# LPS33HW_breakout.net
KiCad netlist of a schematic drawn in EAGLE
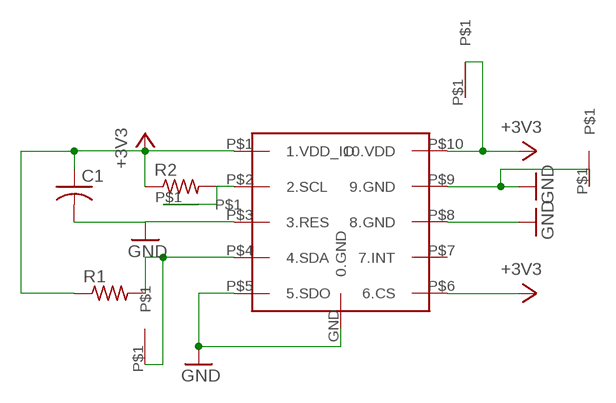
[diagram p0: schematic, sheet 1]

(export (version "E")
  (design (tool "Eeschema 10.0.6"))
  (components
    (comp (ref "C1")
      (value "C-USC0402")
      (footprint "eagle-import:C0402")
      (libsource (lib "eagle-import") (part "C-USC0402"))
    )
    (comp (ref "R1")
      (value "R-US_R0402")
      (footprint "eagle-import:R0402")
      (libsource (lib "eagle-import") (part "R-US_R0402"))
    )
    (comp (ref "R2")
      (value "R-US_R0402")
      (footprint "eagle-import:R0402")
      (libsource (lib "eagle-import") (part "R-US_R0402"))
    )
    (comp (ref "U$1")
      (value "LPS33HW")
      (footprint "eagle-import:LPS33HW")
      (libsource (lib "eagle-import") (part "LPS33HW"))
    )
    (comp (ref "U$2")
      (value "VIA")
      (footprint "eagle-import:VIA")
      (libsource (lib "eagle-import") (part "VIA"))
    )
    (comp (ref "U$3")
      (value "VIA")
      (footprint "eagle-import:VIA")
      (libsource (lib "eagle-import") (part "VIA"))
    )
    (comp (ref "U$4")
      (value "VIA")
      (footprint "eagle-import:VIA")
      (libsource (lib "eagle-import") (part "VIA"))
    )
    (comp (ref "U$5")
      (value "VIA")
      (footprint "eagle-import:VIA")
      (libsource (lib "eagle-import") (part "VIA"))
    )
  )
  (nets
    (net (code "1") (name "+3V3") (class "Default")
      (node (ref "C1") (pin "1") (pinfunction "1_1") (pintype "passive"))
      (node (ref "R1") (pin "1") (pinfunction "1_1") (pintype "passive"))
      (node (ref "R2") (pin "1") (pinfunction "1_1") (pintype "passive"))
      (node (ref "U$1") (pin "P$1") (pinfunction "1.VDD_IO_P$1") (pintype "bidirectional"))
      (node (ref "U$1") (pin "P$10") (pinfunction "10.VDD_P$10") (pintype "bidirectional"))
      (node (ref "U$1") (pin "P$6") (pinfunction "6.CS_P$6") (pintype "bidirectional"))
      (node (ref "U$2") (pin "P$1") (pinfunction "P$1_P$1") (pintype "bidirectional"))
    )
    (net (code "2") (name "GND") (class "Default")
      (node (ref "C1") (pin "2") (pinfunction "2_2") (pintype "passive"))
      (node (ref "U$1") (pin "GND") (pinfunction "0.GND_GND") (pintype "bidirectional"))
      (node (ref "U$1") (pin "P$3") (pinfunction "3.RES_P$3") (pintype "bidirectional"))
      (node (ref "U$1") (pin "P$5") (pinfunction "5.SDO_P$5") (pintype "bidirectional"))
      (node (ref "U$1") (pin "P$8") (pinfunction "8.GND_P$8") (pintype "bidirectional"))
      (node (ref "U$1") (pin "P$9") (pinfunction "9.GND_P$9") (pintype "bidirectional"))
      (node (ref "U$3") (pin "P$1") (pinfunction "P$1_P$1") (pintype "bidirectional"))
    )
    (net (code "3") (name "Net-(U$1-2.SCL)") (class "Default")
      (node (ref "R2") (pin "2") (pinfunction "2_2") (pintype "passive"))
      (node (ref "U$1") (pin "P$2") (pinfunction "2.SCL_P$2") (pintype "bidirectional"))
      (node (ref "U$5") (pin "P$1") (pinfunction "P$1_P$1") (pintype "bidirectional"))
    )
    (net (code "4") (name "Net-(U$1-4.SDA)") (class "Default")
      (node (ref "R1") (pin "2") (pinfunction "2_2") (pintype "passive"))
      (node (ref "U$1") (pin "P$4") (pinfunction "4.SDA_P$4") (pintype "bidirectional"))
      (node (ref "U$4") (pin "P$1") (pinfunction "P$1_P$1") (pintype "bidirectional"))
    )
    (net (code "5") (name "unconnected-(U$1-7.INT-PadP$7)") (class "Default")
      (node (ref "U$1") (pin "P$7") (pinfunction "7.INT_P$7") (pintype "bidirectional"))
    )
  )
)
